# motor_controller.net
KiCad netlist of a schematic drawn in Altium Designer
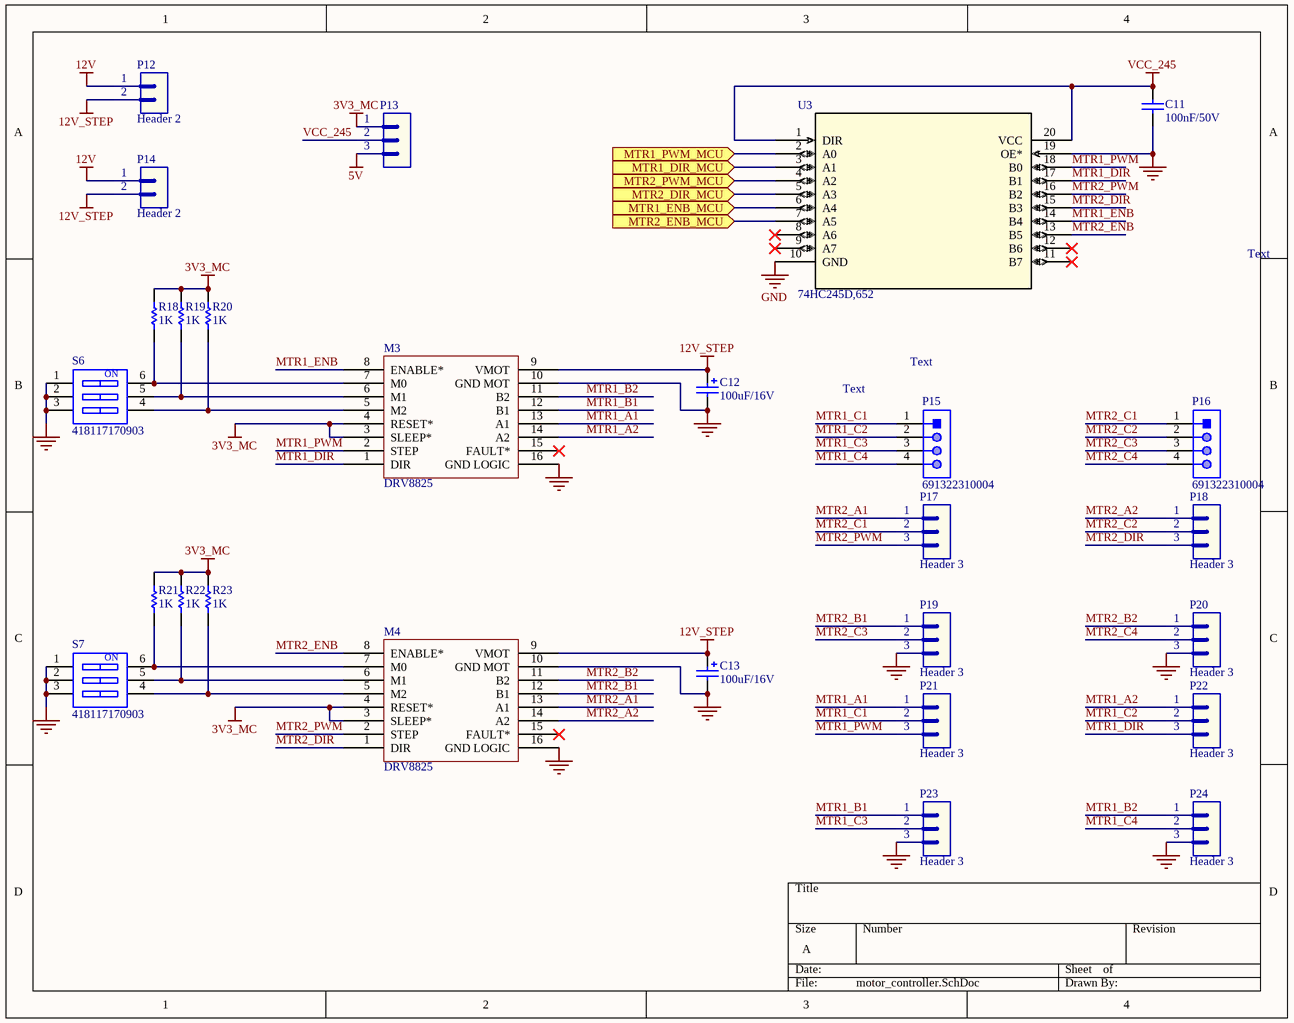
[diagram p0: motor_controller.SchDoc]

(export (version "E")
  (design (tool "Eeschema 10.0.6"))
  (components
    (comp (ref "C11")
      (value "100nF/50V")
      (footprint "CAP-SM-0805")
      (description "CAP CER 0.1UF 50V Y5V 0805")
      (fields
        (field (name "MANUFACTURER") "Samsung Electro-Mechanics")
        (field (name "MANUFACTURER PART NUMBER") "CL21F104ZBCNNNC")
      )
      (libsource (lib "Capacitor") (part "Cap-100nF-50V-0805"))
    )
    (comp (ref "C12")
      (value "100uF/16V")
      (footprint "CAP-SM-AL-SIZE-D-D6L6")
      (description "CAP ALUM 100UF 20% 16V SMD")
      (fields
        (field (name "MANUFACTURER") "Nichicon")
        (field (name "MANUFACTURER PART NUMBER") "UWX1C101MCL1GB")
      )
      (libsource (lib "Capacitor") (part "Cap-Al-100uF-16V-D6L5"))
    )
    (comp (ref "C13")
      (value "100uF/16V")
      (footprint "CAP-SM-AL-SIZE-D-D6L6")
      (description "CAP ALUM 100UF 20% 16V SMD")
      (fields
        (field (name "MANUFACTURER") "Nichicon")
        (field (name "MANUFACTURER PART NUMBER") "UWX1C101MCL1GB")
      )
      (libsource (lib "Capacitor") (part "Cap-Al-100uF-16V-D6L5"))
    )
    (comp (ref "M3") (value "DRV8825") (footprint "DRV8825") (libsource (lib "Schlib1") (part "DRV8825")))
    (comp (ref "M4") (value "DRV8825") (footprint "DRV8825") (libsource (lib "Schlib1") (part "DRV8825")))
    (comp (ref "P12")
      (value "Header 2")
      (footprint "JP2")
      (description "Header, 2-Pin")
      (fields (field (name "PUBLISHER") "Altium Limited"))
      (libsource (lib "PIF_C16_2_lib") (part "Header 2"))
    )
    (comp (ref "P13")
      (value "Header 3")
      (footprint "JP3")
      (description "Header, 3-Pin")
      (fields (field (name "PUBLISHER") "Altium Limited"))
      (libsource (lib "PIF_C16_2_lib") (part "Header 3"))
    )
    (comp (ref "P14")
      (value "Header 2")
      (footprint "JP2")
      (description "Header, 2-Pin")
      (fields (field (name "PUBLISHER") "Altium Limited"))
      (libsource (lib "PIF_C16_2_lib") (part "Header 2"))
    )
    (comp (ref "P15")
      (value "691322310004")
      (footprint "691322310004")
      (description "WR-TBL Serie 322 Horizontal PCB Header, Pluggable, pitch 3.81mm, 4p")
      (fields (field (name "PUBLISHER") "Wurth Elektronik"))
      (libsource (lib "691101710002_Altium_WR-TBL_rev19a") (part "691322310004"))
    )
    (comp (ref "P16")
      (value "691322310004")
      (footprint "691322310004")
      (description "WR-TBL Serie 322 Horizontal PCB Header, Pluggable, pitch 3.81mm, 4p")
      (fields (field (name "PUBLISHER") "Wurth Elektronik"))
      (libsource (lib "691101710002_Altium_WR-TBL_rev19a") (part "691322310004"))
    )
    (comp (ref "P17")
      (value "Header 3")
      (footprint "JP3")
      (description "Header, 3-Pin")
      (fields (field (name "PUBLISHER") "Altium Limited"))
      (libsource (lib "PIF_C16_2_lib") (part "Header 3"))
    )
    (comp (ref "P18")
      (value "Header 3")
      (footprint "JP3")
      (description "Header, 3-Pin")
      (fields (field (name "PUBLISHER") "Altium Limited"))
      (libsource (lib "PIF_C16_2_lib") (part "Header 3"))
    )
    (comp (ref "P19")
      (value "Header 3")
      (footprint "JP3")
      (description "Header, 3-Pin")
      (fields (field (name "PUBLISHER") "Altium Limited"))
      (libsource (lib "PIF_C16_2_lib") (part "Header 3"))
    )
    (comp (ref "P20")
      (value "Header 3")
      (footprint "JP3")
      (description "Header, 3-Pin")
      (fields (field (name "PUBLISHER") "Altium Limited"))
      (libsource (lib "PIF_C16_2_lib") (part "Header 3"))
    )
    (comp (ref "P21")
      (value "Header 3")
      (footprint "JP3")
      (description "Header, 3-Pin")
      (fields (field (name "PUBLISHER") "Altium Limited"))
      (libsource (lib "PIF_C16_2_lib") (part "Header 3"))
    )
    (comp (ref "P22")
      (value "Header 3")
      (footprint "JP3")
      (description "Header, 3-Pin")
      (fields (field (name "PUBLISHER") "Altium Limited"))
      (libsource (lib "PIF_C16_2_lib") (part "Header 3"))
    )
    (comp (ref "P23")
      (value "Header 3")
      (footprint "JP3")
      (description "Header, 3-Pin")
      (fields (field (name "PUBLISHER") "Altium Limited"))
      (libsource (lib "PIF_C16_2_lib") (part "Header 3"))
    )
    (comp (ref "P24")
      (value "Header 3")
      (footprint "JP3")
      (description "Header, 3-Pin")
      (fields (field (name "PUBLISHER") "Altium Limited"))
      (libsource (lib "PIF_C16_2_lib") (part "Header 3"))
    )
    (comp (ref "R18")
      (value "1K")
      (footprint "Resistor:RES-SM-0805")
      (description "RES 1K OHM 1% 1/4W 0805")
      (fields
        (field (name "MANUFACTURER") "Stackpole Electronics Inc")
        (field (name "MANUFACTURER PART NUMBER") "RNCP0805FTD1K00")
      )
      (libsource (lib "Resistor") (part "Res-1K-0805"))
    )
    (comp (ref "R19")
      (value "1K")
      (footprint "Resistor:RES-SM-0805")
      (description "RES 1K OHM 1% 1/4W 0805")
      (fields
        (field (name "MANUFACTURER") "Stackpole Electronics Inc")
        (field (name "MANUFACTURER PART NUMBER") "RNCP0805FTD1K00")
      )
      (libsource (lib "Resistor") (part "Res-1K-0805"))
    )
    (comp (ref "R20")
      (value "1K")
      (footprint "Resistor:RES-SM-0805")
      (description "RES 1K OHM 1% 1/4W 0805")
      (fields
        (field (name "MANUFACTURER") "Stackpole Electronics Inc")
        (field (name "MANUFACTURER PART NUMBER") "RNCP0805FTD1K00")
      )
      (libsource (lib "Resistor") (part "Res-1K-0805"))
    )
    (comp (ref "R21")
      (value "1K")
      (footprint "Resistor:RES-SM-0805")
      (description "RES 1K OHM 1% 1/4W 0805")
      (fields
        (field (name "MANUFACTURER") "Stackpole Electronics Inc")
        (field (name "MANUFACTURER PART NUMBER") "RNCP0805FTD1K00")
      )
      (libsource (lib "Resistor") (part "Res-1K-0805"))
    )
    (comp (ref "R22")
      (value "1K")
      (footprint "Resistor:RES-SM-0805")
      (description "RES 1K OHM 1% 1/4W 0805")
      (fields
        (field (name "MANUFACTURER") "Stackpole Electronics Inc")
        (field (name "MANUFACTURER PART NUMBER") "RNCP0805FTD1K00")
      )
      (libsource (lib "Resistor") (part "Res-1K-0805"))
    )
    (comp (ref "R23")
      (value "1K")
      (footprint "Resistor:RES-SM-0805")
      (description "RES 1K OHM 1% 1/4W 0805")
      (fields
        (field (name "MANUFACTURER") "Stackpole Electronics Inc")
        (field (name "MANUFACTURER PART NUMBER") "RNCP0805FTD1K00")
      )
      (libsource (lib "Resistor") (part "Res-1K-0805"))
    )
    (comp (ref "S6")
      (value "418117170903")
      (footprint "418117170903")
      (description "WS-DITV Compact THT Dip Switch, Flat Actuator, pitch 2.54mm, 3p")
      (fields (field (name "PUBLISHER") "Wurth Elektronik"))
      (libsource (lib "418117170903_Altium_WS-DITV_rev19a") (part "418117170903"))
    )
    (comp (ref "S7")
      (value "418117170903")
      (footprint "418117170903")
      (description "WS-DITV Compact THT Dip Switch, Flat Actuator, pitch 2.54mm, 3p")
      (fields (field (name "PUBLISHER") "Wurth Elektronik"))
      (libsource (lib "418117170903_Altium_WS-DITV_rev19a") (part "418117170903"))
    )
    (comp (ref "U3")
      (value "74HC245D,652")
      (footprint "SOT163-1_NEX")
      (description "No Description Available")
      (fields (field (name "COPYRIGHT") "Copyright (C) 2016 Accelerated Designs. All rights reserved"))
      (libsource (lib "Schlib1") (part "74HC245D,652"))
    )
  )
  (nets
    (net (code "1") (name "/MTR1_A1") (class "Default")
      (node (ref "M3") (pin "13") (pinfunction "A1_13") (pintype "passive"))
      (node (ref "P21") (pin "1") (pinfunction "1_1") (pintype "passive"))
    )
    (net (code "2") (name "/MTR1_A2") (class "Default")
      (node (ref "M3") (pin "14") (pinfunction "A2_14") (pintype "passive"))
      (node (ref "P22") (pin "1") (pinfunction "1_1") (pintype "passive"))
    )
    (net (code "3") (name "/MTR1_B1") (class "Default")
      (node (ref "M3") (pin "12") (pinfunction "B1_12") (pintype "passive"))
      (node (ref "P23") (pin "1") (pinfunction "1_1") (pintype "passive"))
    )
    (net (code "4") (name "/MTR1_B2") (class "Default")
      (node (ref "M3") (pin "11") (pinfunction "B2_11") (pintype "passive"))
      (node (ref "P24") (pin "1") (pinfunction "1_1") (pintype "passive"))
    )
    (net (code "5") (name "/MTR1_C1") (class "Default")
      (node (ref "P15") (pin "1") (pinfunction "1_1") (pintype "passive"))
      (node (ref "P21") (pin "2") (pinfunction "2_2") (pintype "passive"))
    )
    (net (code "6") (name "/MTR1_C2") (class "Default")
      (node (ref "P15") (pin "2") (pinfunction "2_2") (pintype "passive"))
      (node (ref "P22") (pin "2") (pinfunction "2_2") (pintype "passive"))
    )
    (net (code "7") (name "/MTR1_C3") (class "Default")
      (node (ref "P15") (pin "3") (pinfunction "3_3") (pintype "passive"))
      (node (ref "P23") (pin "2") (pinfunction "2_2") (pintype "passive"))
    )
    (net (code "8") (name "/MTR1_C4") (class "Default")
      (node (ref "P15") (pin "4") (pinfunction "4_4") (pintype "passive"))
      (node (ref "P24") (pin "2") (pinfunction "2_2") (pintype "passive"))
    )
    (net (code "9") (name "/MTR1_DIR") (class "Default")
      (node (ref "M3") (pin "1") (pinfunction "DIR_1") (pintype "passive"))
      (node (ref "P22") (pin "3") (pinfunction "3_3") (pintype "passive"))
      (node (ref "U3") (pin "17") (pinfunction "B1_17") (pintype "bidirectional"))
    )
    (net (code "10") (name "/MTR1_DIR_MCU") (class "Default")
      (node (ref "U3") (pin "3") (pinfunction "A1_3") (pintype "bidirectional"))
    )
    (net (code "11") (name "/MTR1_ENB") (class "Default")
      (node (ref "M3") (pin "8") (pinfunction "ENABLE*_8") (pintype "passive"))
      (node (ref "U3") (pin "14") (pinfunction "B4_14") (pintype "bidirectional"))
    )
    (net (code "12") (name "/MTR1_ENB_MCU") (class "Default")
      (node (ref "U3") (pin "6") (pinfunction "A4_6") (pintype "bidirectional"))
    )
    (net (code "13") (name "/MTR1_PWM") (class "Default")
      (node (ref "M3") (pin "2") (pinfunction "STEP_2") (pintype "passive"))
      (node (ref "P21") (pin "3") (pinfunction "3_3") (pintype "passive"))
      (node (ref "U3") (pin "18") (pinfunction "B0_18") (pintype "bidirectional"))
    )
    (net (code "14") (name "/MTR1_PWM_MCU") (class "Default")
      (node (ref "U3") (pin "2") (pinfunction "A0_2") (pintype "bidirectional"))
    )
    (net (code "15") (name "/MTR2_A1") (class "Default")
      (node (ref "M4") (pin "13") (pinfunction "A1_13") (pintype "passive"))
      (node (ref "P17") (pin "1") (pinfunction "1_1") (pintype "passive"))
    )
    (net (code "16") (name "/MTR2_A2") (class "Default")
      (node (ref "M4") (pin "14") (pinfunction "A2_14") (pintype "passive"))
      (node (ref "P18") (pin "1") (pinfunction "1_1") (pintype "passive"))
    )
    (net (code "17") (name "/MTR2_B1") (class "Default")
      (node (ref "M4") (pin "12") (pinfunction "B1_12") (pintype "passive"))
      (node (ref "P19") (pin "1") (pinfunction "1_1") (pintype "passive"))
    )
    (net (code "18") (name "/MTR2_B2") (class "Default")
      (node (ref "M4") (pin "11") (pinfunction "B2_11") (pintype "passive"))
      (node (ref "P20") (pin "1") (pinfunction "1_1") (pintype "passive"))
    )
    (net (code "19") (name "/MTR2_C1") (class "Default")
      (node (ref "P16") (pin "1") (pinfunction "1_1") (pintype "passive"))
      (node (ref "P17") (pin "2") (pinfunction "2_2") (pintype "passive"))
    )
    (net (code "20") (name "/MTR2_C2") (class "Default")
      (node (ref "P16") (pin "2") (pinfunction "2_2") (pintype "passive"))
      (node (ref "P18") (pin "2") (pinfunction "2_2") (pintype "passive"))
    )
    (net (code "21") (name "/MTR2_C3") (class "Default")
      (node (ref "P16") (pin "3") (pinfunction "3_3") (pintype "passive"))
      (node (ref "P19") (pin "2") (pinfunction "2_2") (pintype "passive"))
    )
    (net (code "22") (name "/MTR2_C4") (class "Default")
      (node (ref "P16") (pin "4") (pinfunction "4_4") (pintype "passive"))
      (node (ref "P20") (pin "2") (pinfunction "2_2") (pintype "passive"))
    )
    (net (code "23") (name "/MTR2_DIR") (class "Default")
      (node (ref "M4") (pin "1") (pinfunction "DIR_1") (pintype "passive"))
      (node (ref "P18") (pin "3") (pinfunction "3_3") (pintype "passive"))
      (node (ref "U3") (pin "15") (pinfunction "B3_15") (pintype "bidirectional"))
    )
    (net (code "24") (name "/MTR2_DIR_MCU") (class "Default")
      (node (ref "U3") (pin "5") (pinfunction "A3_5") (pintype "bidirectional"))
    )
    (net (code "25") (name "/MTR2_ENB") (class "Default")
      (node (ref "M4") (pin "8") (pinfunction "ENABLE*_8") (pintype "passive"))
      (node (ref "U3") (pin "13") (pinfunction "B5_13") (pintype "bidirectional"))
    )
    (net (code "26") (name "/MTR2_ENB_MCU") (class "Default")
      (node (ref "U3") (pin "7") (pinfunction "A5_7") (pintype "bidirectional"))
    )
    (net (code "27") (name "/MTR2_PWM") (class "Default")
      (node (ref "M4") (pin "2") (pinfunction "STEP_2") (pintype "passive"))
      (node (ref "P17") (pin "3") (pinfunction "3_3") (pintype "passive"))
      (node (ref "U3") (pin "16") (pinfunction "B2_16") (pintype "bidirectional"))
    )
    (net (code "28") (name "/MTR2_PWM_MCU") (class "Default")
      (node (ref "U3") (pin "4") (pinfunction "A2_4") (pintype "bidirectional"))
    )
    (net (code "29") (name "3V3_MC") (class "Default")
      (node (ref "M3") (pin "3") (pinfunction "SLEEP*_3") (pintype "passive"))
      (node (ref "M3") (pin "4") (pinfunction "RESET*_4") (pintype "passive"))
      (node (ref "M4") (pin "3") (pinfunction "SLEEP*_3") (pintype "passive"))
      (node (ref "M4") (pin "4") (pinfunction "RESET*_4") (pintype "passive"))
      (node (ref "P13") (pin "1") (pinfunction "1_1") (pintype "passive"))
      (node (ref "R18") (pin "2") (pinfunction "2_2") (pintype "passive"))
      (node (ref "R19") (pin "2") (pinfunction "2_2") (pintype "passive"))
      (node (ref "R20") (pin "2") (pinfunction "2_2") (pintype "passive"))
      (node (ref "R21") (pin "2") (pinfunction "2_2") (pintype "passive"))
      (node (ref "R22") (pin "2") (pinfunction "2_2") (pintype "passive"))
      (node (ref "R23") (pin "2") (pinfunction "2_2") (pintype "passive"))
    )
    (net (code "30") (name "5V") (class "Default")
      (node (ref "P13") (pin "3") (pinfunction "3_3") (pintype "passive"))
    )
    (net (code "31") (name "12V") (class "Default")
      (node (ref "P12") (pin "1") (pinfunction "1_1") (pintype "passive"))
      (node (ref "P14") (pin "1") (pinfunction "1_1") (pintype "passive"))
    )
    (net (code "32") (name "12V_STEP") (class "Default")
      (node (ref "C12") (pin "1") (pinfunction "1_1") (pintype "passive"))
      (node (ref "C13") (pin "1") (pinfunction "1_1") (pintype "passive"))
      (node (ref "M3") (pin "9") (pinfunction "VMOT_9") (pintype "passive"))
      (node (ref "M4") (pin "9") (pinfunction "VMOT_9") (pintype "passive"))
      (node (ref "P12") (pin "2") (pinfunction "2_2") (pintype "passive"))
      (node (ref "P14") (pin "2") (pinfunction "2_2") (pintype "passive"))
    )
    (net (code "33") (name "GND") (class "Default")
      (node (ref "C11") (pin "1") (pinfunction "1_1") (pintype "passive"))
      (node (ref "C12") (pin "2") (pinfunction "2_2") (pintype "passive"))
      (node (ref "C13") (pin "2") (pinfunction "2_2") (pintype "passive"))
      (node (ref "M3") (pin "10") (pinfunction "GND_MOT_10") (pintype "passive"))
      (node (ref "M3") (pin "16") (pinfunction "GND_LOGIC_16") (pintype "passive"))
      (node (ref "M4") (pin "10") (pinfunction "GND_MOT_10") (pintype "passive"))
      (node (ref "M4") (pin "16") (pinfunction "GND_LOGIC_16") (pintype "passive"))
      (node (ref "P19") (pin "3") (pinfunction "3_3") (pintype "passive"))
      (node (ref "P20") (pin "3") (pinfunction "3_3") (pintype "passive"))
      (node (ref "P23") (pin "3") (pinfunction "3_3") (pintype "passive"))
      (node (ref "P24") (pin "3") (pinfunction "3_3") (pintype "passive"))
      (node (ref "S6") (pin "1") (pinfunction "1_1") (pintype "passive"))
      (node (ref "S6") (pin "2") (pinfunction "2_2") (pintype "passive"))
      (node (ref "S6") (pin "3") (pinfunction "3_3") (pintype "passive"))
      (node (ref "S7") (pin "1") (pinfunction "1_1") (pintype "passive"))
      (node (ref "S7") (pin "2") (pinfunction "2_2") (pintype "passive"))
      (node (ref "S7") (pin "3") (pinfunction "3_3") (pintype "passive"))
      (node (ref "U3") (pin "10") (pinfunction "GND_10") (pintype "power_in"))
      (node (ref "U3") (pin "19") (pinfunction "OE*_19") (pintype "input"))
    )
    (net (code "34") (name "Net-(M3-M0)") (class "Default")
      (node (ref "M3") (pin "7") (pinfunction "M0_7") (pintype "passive"))
      (node (ref "R18") (pin "1") (pinfunction "1_1") (pintype "passive"))
      (node (ref "S6") (pin "6") (pinfunction "6_6") (pintype "passive"))
    )
    (net (code "35") (name "Net-(M3-M1)") (class "Default")
      (node (ref "M3") (pin "6") (pinfunction "M1_6") (pintype "passive"))
      (node (ref "R19") (pin "1") (pinfunction "1_1") (pintype "passive"))
      (node (ref "S6") (pin "5") (pinfunction "5_5") (pintype "passive"))
    )
    (net (code "36") (name "Net-(M3-M2)") (class "Default")
      (node (ref "M3") (pin "5") (pinfunction "M2_5") (pintype "passive"))
      (node (ref "R20") (pin "1") (pinfunction "1_1") (pintype "passive"))
      (node (ref "S6") (pin "4") (pinfunction "4_4") (pintype "passive"))
    )
    (net (code "37") (name "Net-(M4-M0)") (class "Default")
      (node (ref "M4") (pin "7") (pinfunction "M0_7") (pintype "passive"))
      (node (ref "R21") (pin "1") (pinfunction "1_1") (pintype "passive"))
      (node (ref "S7") (pin "6") (pinfunction "6_6") (pintype "passive"))
    )
    (net (code "38") (name "Net-(M4-M1)") (class "Default")
      (node (ref "M4") (pin "6") (pinfunction "M1_6") (pintype "passive"))
      (node (ref "R22") (pin "1") (pinfunction "1_1") (pintype "passive"))
      (node (ref "S7") (pin "5") (pinfunction "5_5") (pintype "passive"))
    )
    (net (code "39") (name "Net-(M4-M2)") (class "Default")
      (node (ref "M4") (pin "5") (pinfunction "M2_5") (pintype "passive"))
      (node (ref "R23") (pin "1") (pinfunction "1_1") (pintype "passive"))
      (node (ref "S7") (pin "4") (pinfunction "4_4") (pintype "passive"))
    )
    (net (code "40") (name "VCC_245") (class "Default")
      (node (ref "C11") (pin "2") (pinfunction "2_2") (pintype "passive"))
      (node (ref "P13") (pin "2") (pinfunction "2_2") (pintype "passive"))
      (node (ref "U3") (pin "1") (pinfunction "DIR_1") (pintype "input"))
      (node (ref "U3") (pin "20") (pinfunction "VCC_20") (pintype "power_in"))
    )
    (net (code "41") (name "unconnected-(M3-FAULT*-Pad15)") (class "Default")
      (node (ref "M3") (pin "15") (pinfunction "FAULT*_15") (pintype "passive+no_connect"))
    )
    (net (code "42") (name "unconnected-(M4-FAULT*-Pad15)") (class "Default")
      (node (ref "M4") (pin "15") (pinfunction "FAULT*_15") (pintype "passive+no_connect"))
    )
    (net (code "43") (name "unconnected-(U3-A6-Pad8)") (class "Default")
      (node (ref "U3") (pin "8") (pinfunction "A6_8") (pintype "bidirectional+no_connect"))
    )
    (net (code "44") (name "unconnected-(U3-A7-Pad9)") (class "Default")
      (node (ref "U3") (pin "9") (pinfunction "A7_9") (pintype "bidirectional+no_connect"))
    )
    (net (code "45") (name "unconnected-(U3-B6-Pad12)") (class "Default")
      (node (ref "U3") (pin "12") (pinfunction "B6_12") (pintype "bidirectional+no_connect"))
    )
    (net (code "46") (name "unconnected-(U3-B7-Pad11)") (class "Default")
      (node (ref "U3") (pin "11") (pinfunction "B7_11") (pintype "bidirectional+no_connect"))
    )
  )
)
